# Stepping_Motor_DriverE.net
KiCad netlist of a schematic drawn in Altium Designer
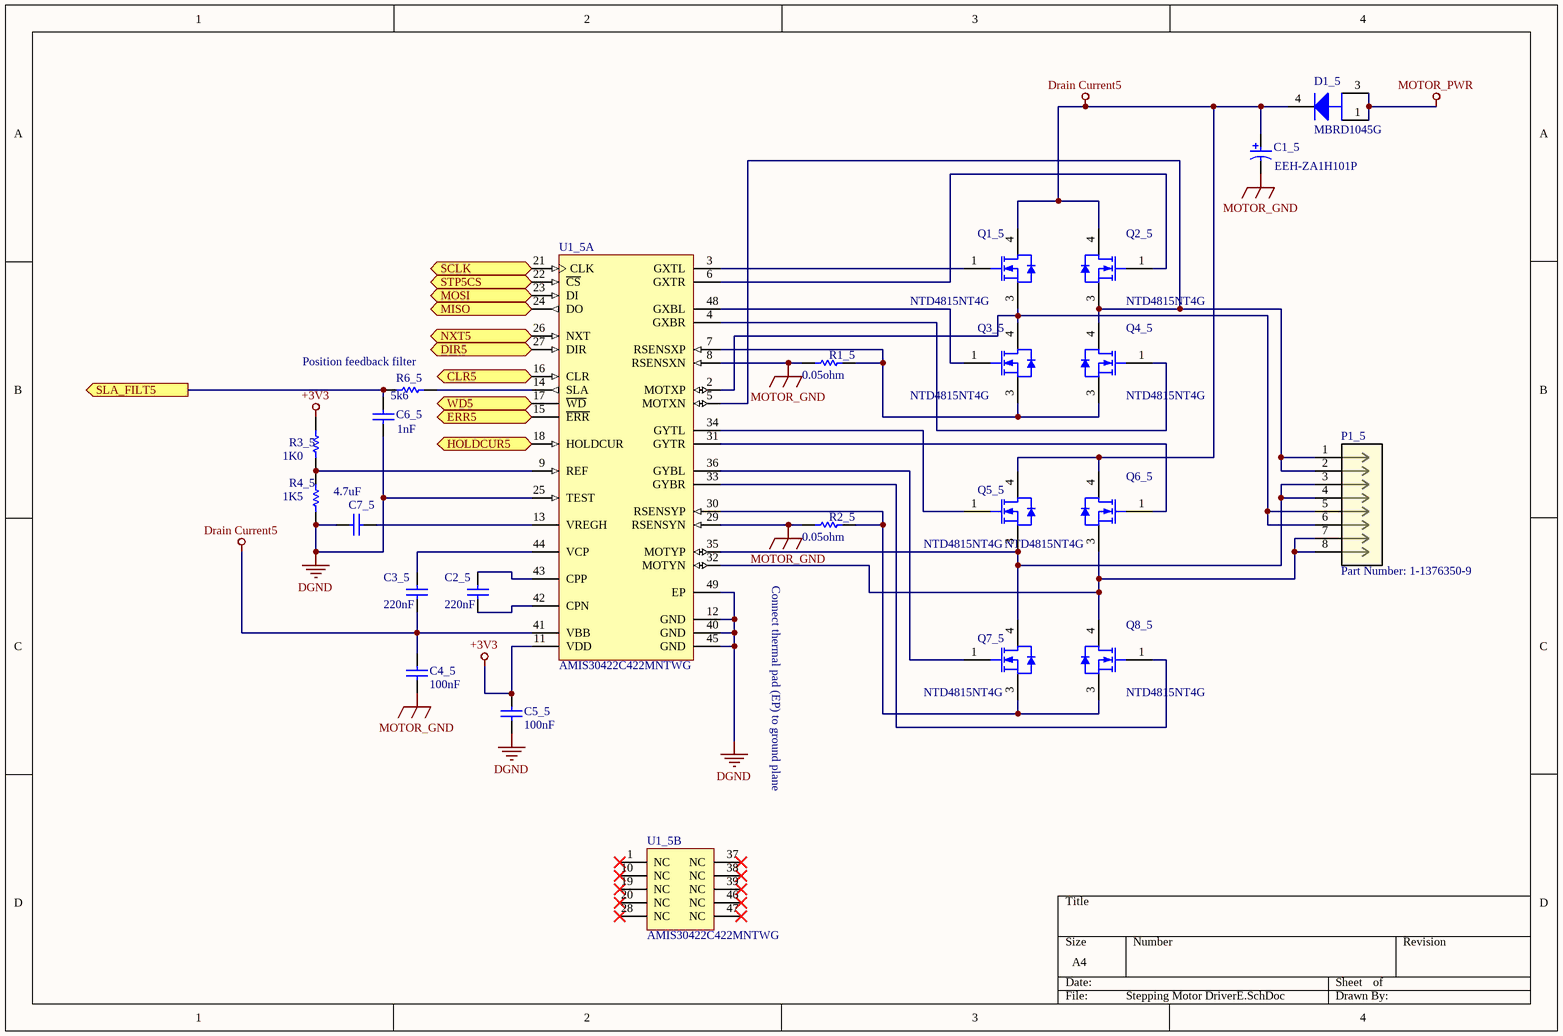
[diagram p0: Stepping Motor DriverE.SchDoc]

(export (version "E")
  (design (tool "Eeschema 10.0.6"))
  (components
    (comp (ref "C1_5")
      (value "EEH-ZA1H101P")
      (footprint "PNSC-ZA-G_L")
      (fields (field (name "TOLERANCE") "20%") (field (name "MANUFACTURER") "Panasonic"))
      (libsource (lib "Altium Content Vault") (part "CAP-P-2"))
    )
    (comp (ref "C2_5")
      (value "220nF")
      (footprint "CAPC0805(2012)75_L")
      (description "CAP 220nF 50V -20% to +80% 0805 (2012 Metric) Thickness 0.75mm SMD")
      (fields (field (name "TOLERANCE") "-20% to +80%") (field (name "Comment") "CAP 220nF 50V 0805(2012)"))
      (libsource (lib "Altium Content Vault") (part "CMP-1036-04556-1"))
    )
    (comp (ref "C3_5")
      (value "220nF")
      (footprint "CAPC0805(2012)75_L")
      (description "CAP 220nF 50V -20% to +80% 0805 (2012 Metric) Thickness 0.75mm SMD")
      (fields (field (name "TOLERANCE") "-20% to +80%") (field (name "Comment") "CAP 220nF 50V 0805(2012)"))
      (libsource (lib "Altium Content Vault") (part "CMP-1036-04556-1"))
    )
    (comp (ref "C4_5")
      (value "100nF")
      (footprint "CAPC1812(4532)110_N")
      (description "CAP 100nF 50V ±20% 1812 (4532 Metric) Thickness 1.1mm SMD")
      (fields (field (name "TOLERANCE") "Â±20%") (field (name "Comment") "CAP 100nF 50V 1812(4532)"))
      (libsource (lib "Altium Content Vault") (part "CMP-1040-01292-1"))
    )
    (comp (ref "C5_5")
      (value "100nF")
      (footprint "CAPC1812(4532)110_N")
      (description "CAP 100nF 50V ±20% 1812 (4532 Metric) Thickness 1.1mm SMD")
      (fields (field (name "TOLERANCE") "Â±20%") (field (name "Comment") "CAP 100nF 50V 1812(4532)"))
      (libsource (lib "Altium Content Vault") (part "CMP-1040-01292-1"))
    )
    (comp (ref "C6_5")
      (value "1nF")
      (footprint "CAPC1206(3216)170_N")
      (description "CAP 1nF 50V ±2% 1206 (3216 Metric) Thickness 1.7mm SMD")
      (fields (field (name "TOLERANCE") "Â±2%") (field (name "Comment") "CAP 1nF 50V 1206(3216)"))
      (libsource (lib "Altium Content Vault") (part "CMP-1037-02447-1"))
    )
    (comp (ref "C7_5")
      (value "4.7uF")
      (footprint "CAPC2220(5750)230_L")
      (description "CAP 4.7uF 50V ±10% 2220 (5750 Metric) Thickness 2.2mm SMD")
      (fields (field (name "TOLERANCE") "Â±10%") (field (name "Comment") "CAP 4.7uF 50V 2220(5750)"))
      (libsource (lib "Altium Content Vault") (part "CMP-1042-00755-1"))
    )
    (comp (ref "D1_5")
      (value "MBRD1045G")
      (footprint "ONSC-DPAK-3-369C-01_V")
      (description "SWITCHMODE(TM) Schottky Power Rectifier, 3-Pin DPAK, Pb-Free, Tube")
      (fields (field (name "MANUFACTURER") "On Semiconductor"))
      (libsource (lib "Altium Content Vault") (part "ONSC-D-A1A3K4-3_A"))
    )
    (comp (ref "P1_5")
      (value "Part Number: 1-1376350-9")
      (footprint "conn8_1-1376350-")
      (description "025 8POS CAP ASSY H TIN")
      (fields
        (field (name "MANUFACTURER_PART_NUMBER") "1-1376350-9")
        (field (name "COPYRIGHT") "Copyright (C) 2018 Accelerated Designs. All rights reserved")
      )
      (libsource (lib "2020-04-08_04-40-03") (part "1-1376350-9"))
    )
    (comp (ref "Q1_5")
      (value "NTD4815NT4G")
      (footprint "ONSC-DPAK-3-369AA-01_V")
      (description "Power MOSFET, 30 V, 35 A, Single N-Channel, 3-Pin DPAK, Pb-Free, Tape and Reel")
      (fields (field (name "MANUFACTURER") "On Semiconductor"))
      (libsource (lib "Altium Content Vault") (part "ONSC-NMOS-G1S3D4-3_B"))
    )
    (comp (ref "Q2_5")
      (value "NTD4815NT4G")
      (footprint "ONSC-DPAK-3-369AA-01_V")
      (description "Power MOSFET, 30 V, 35 A, Single N-Channel, 3-Pin DPAK, Pb-Free, Tape and Reel")
      (fields (field (name "MANUFACTURER") "On Semiconductor"))
      (libsource (lib "Altium Content Vault") (part "CMP-1058-00298-1"))
    )
    (comp (ref "Q3_5")
      (value "NTD4815NT4G")
      (footprint "ONSC-DPAK-3-369AA-01_V")
      (description "Power MOSFET, 30 V, 35 A, Single N-Channel, 3-Pin DPAK, Pb-Free, Tape and Reel")
      (fields (field (name "MANUFACTURER") "On Semiconductor"))
      (libsource (lib "Altium Content Vault") (part "ONSC-NMOS-G1S3D4-3_B"))
    )
    (comp (ref "Q4_5")
      (value "NTD4815NT4G")
      (footprint "ONSC-DPAK-3-369AA-01_V")
      (description "Power MOSFET, 30 V, 35 A, Single N-Channel, 3-Pin DPAK, Pb-Free, Tape and Reel")
      (fields (field (name "MANUFACTURER") "On Semiconductor"))
      (libsource (lib "Altium Content Vault") (part "CMP-1058-00298-1"))
    )
    (comp (ref "Q5_5")
      (value "NTD4815NT4G")
      (footprint "ONSC-DPAK-3-369AA-01_V")
      (description "Power MOSFET, 30 V, 35 A, Single N-Channel, 3-Pin DPAK, Pb-Free, Tape and Reel")
      (fields (field (name "MANUFACTURER") "On Semiconductor"))
      (libsource (lib "Altium Content Vault") (part "ONSC-NMOS-G1S3D4-3_B"))
    )
    (comp (ref "Q6_5")
      (value "NTD4815NT4G")
      (footprint "ONSC-DPAK-3-369AA-01_V")
      (description "Power MOSFET, 30 V, 35 A, Single N-Channel, 3-Pin DPAK, Pb-Free, Tape and Reel")
      (fields (field (name "MANUFACTURER") "On Semiconductor"))
      (libsource (lib "Altium Content Vault") (part "CMP-1058-00298-1"))
    )
    (comp (ref "Q7_5")
      (value "NTD4815NT4G")
      (footprint "ONSC-DPAK-3-369AA-01_V")
      (description "Power MOSFET, 30 V, 35 A, Single N-Channel, 3-Pin DPAK, Pb-Free, Tape and Reel")
      (fields (field (name "MANUFACTURER") "On Semiconductor"))
      (libsource (lib "Altium Content Vault") (part "ONSC-NMOS-G1S3D4-3_B"))
    )
    (comp (ref "Q8_5")
      (value "NTD4815NT4G")
      (footprint "ONSC-DPAK-3-369AA-01_V")
      (description "Power MOSFET, 30 V, 35 A, Single N-Channel, 3-Pin DPAK, Pb-Free, Tape and Reel")
      (fields (field (name "MANUFACTURER") "On Semiconductor"))
      (libsource (lib "Altium Content Vault") (part "CMP-1058-00298-1"))
    )
    (comp (ref "R1_5")
      (value "WSL2512R0500FEA")
      (footprint "RESC6432X89X76LL25T25")
      (description "Chip Resistor, 50 mOhm, +/- 1%, 1 W, -65 to 170 degC, 2512 (6432 Metric), RoHS, Tape and Reel")
      (fields (field (name "MANUFACTURER") "Vishay") (field (name "RESISTANCE") "0.05ohm"))
      (libsource (lib "Altium Content Vault") (part "CMP-2000-07420-1"))
    )
    (comp (ref "R2_5")
      (value "WSL2512R0500FEA")
      (footprint "RESC6432X89X76LL25T25")
      (description "Chip Resistor, 50 mOhm, +/- 1%, 1 W, -65 to 170 degC, 2512 (6432 Metric), RoHS, Tape and Reel")
      (fields (field (name "MANUFACTURER") "Vishay") (field (name "RESISTANCE") "0.05ohm"))
      (libsource (lib "Altium Content Vault") (part "CMP-2000-07420-1"))
    )
    (comp (ref "R3_5")
      (value "1K0")
      (footprint "RESC0805(2012)_M")
      (description "1K 0.125W 1% 0805 (2012 Metric)  SMD")
      (fields (field (name "TOLERANCE") "1 %") (field (name "POWER") "0.125 W"))
      (libsource (lib "Altium Content Vault") (part "CMP-1013-00510-1"))
    )
    (comp (ref "R4_5")
      (value "1K5")
      (footprint "RESC0805(2012)_M")
      (description "1K5 0.125W 1% 0805 (2012 Metric)  SMD")
      (fields (field (name "POWER") "0.125 W") (field (name "TOLERANCE") "1 %"))
      (libsource (lib "Altium Content Vault") (part "CMP-1013-00528-1"))
    )
    (comp (ref "R6_5")
      (value "5k6")
      (footprint "RESC0805(2012)_L")
      (description "5K6 0.125W 1% 0805 (2012 Metric)  SMD")
      (fields (field (name "POWER") "0.125 W") (field (name "TOLERANCE") "1 %"))
      (libsource (lib "Altium Content Vault") (part "CMP-1013-00595-1"))
    )
    (comp (ref "U1_5")
      (value "AMIS30422C422MNTWG")
      (footprint "ONSC-QFN-48-485AJ-01_V")
      (fields (field (name "MANUFACTURER") "ON Semiconductor"))
      (libsource (lib "Altium Content Vault") (part "ONSC-AMIS-30422-QFN-48"))
    )
  )
  (nets
    (net (code "1") (name "+3V3") (class "Default")
      (node (ref "C5_5") (pin "2") (pinfunction "2_2") (pintype "passive"))
      (node (ref "R3_5") (pin "2") (pinfunction "2_2") (pintype "passive"))
      (node (ref "U1_5") (pin "11") (pinfunction "VDD_11") (pintype "power_in"))
    )
    (net (code "2") (name "/CLR5") (class "Default")
      (node (ref "U1_5") (pin "16") (pinfunction "CLR_16") (pintype "input"))
    )
    (net (code "3") (name "/DIR5") (class "Default")
      (node (ref "U1_5") (pin "27") (pinfunction "DIR_27") (pintype "input"))
    )
    (net (code "4") (name "/ERR5") (class "Default")
      (node (ref "U1_5") (pin "15") (pinfunction "~{ERR}_15") (pintype "tri_state"))
    )
    (net (code "5") (name "/HOLDCUR5") (class "Default")
      (node (ref "U1_5") (pin "18") (pinfunction "HOLDCUR_18") (pintype "input"))
    )
    (net (code "6") (name "/MISO") (class "Default")
      (node (ref "U1_5") (pin "24") (pinfunction "DO_24") (pintype "output"))
    )
    (net (code "7") (name "/MOSI") (class "Default")
      (node (ref "U1_5") (pin "23") (pinfunction "DI_23") (pintype "input"))
    )
    (net (code "8") (name "/NXT5") (class "Default")
      (node (ref "U1_5") (pin "26") (pinfunction "NXT_26") (pintype "input"))
    )
    (net (code "9") (name "/SCLK") (class "Default")
      (node (ref "U1_5") (pin "21") (pinfunction "CLK_21") (pintype "input"))
    )
    (net (code "10") (name "/SLA_FILT5") (class "Default")
      (node (ref "C6_5") (pin "2") (pinfunction "2_2") (pintype "passive"))
      (node (ref "R6_5") (pin "1") (pinfunction "1_1") (pintype "passive"))
    )
    (net (code "11") (name "/STP5CS") (class "Default")
      (node (ref "U1_5") (pin "22") (pinfunction "~{CS}_22") (pintype "input"))
    )
    (net (code "12") (name "/WD5") (class "Default")
      (node (ref "U1_5") (pin "17") (pinfunction "~{WD}_17") (pintype "tri_state"))
    )
    (net (code "13") (name "DGND") (class "Default")
      (node (ref "C5_5") (pin "1") (pinfunction "1_1") (pintype "passive"))
      (node (ref "C6_5") (pin "1") (pinfunction "1_1") (pintype "passive"))
      (node (ref "C7_5") (pin "1") (pinfunction "1_1") (pintype "passive"))
      (node (ref "R4_5") (pin "1") (pinfunction "1_1") (pintype "passive"))
      (node (ref "U1_5") (pin "12") (pinfunction "GND_12") (pintype "power_in"))
      (node (ref "U1_5") (pin "25") (pinfunction "TEST_25") (pintype "input"))
      (node (ref "U1_5") (pin "40") (pinfunction "GND_40") (pintype "power_in"))
      (node (ref "U1_5") (pin "45") (pinfunction "GND_45") (pintype "power_in"))
      (node (ref "U1_5") (pin "49") (pinfunction "EP_49") (pintype "passive"))
    )
    (net (code "14") (name "Drain Current5") (class "Default")
      (node (ref "C1_5") (pin "1") (pinfunction "1_1") (pintype "passive"))
      (node (ref "C3_5") (pin "1") (pinfunction "1_1") (pintype "passive"))
      (node (ref "C4_5") (pin "2") (pinfunction "2_2") (pintype "passive"))
      (node (ref "D1_5") (pin "4") (pinfunction "K_4") (pintype "passive"))
      (node (ref "Q1_5") (pin "4") (pinfunction "D_4") (pintype "passive"))
      (node (ref "Q2_5") (pin "4") (pinfunction "D_4") (pintype "passive"))
      (node (ref "Q5_5") (pin "4") (pinfunction "D_4") (pintype "passive"))
      (node (ref "Q6_5") (pin "4") (pinfunction "D_4") (pintype "passive"))
      (node (ref "U1_5") (pin "41") (pinfunction "VBB_41") (pintype "power_in"))
    )
    (net (code "15") (name "MOTOR_GND") (class "Default")
      (node (ref "C1_5") (pin "2") (pinfunction "2_2") (pintype "passive"))
      (node (ref "C4_5") (pin "1") (pinfunction "1_1") (pintype "passive"))
      (node (ref "R1_5") (pin "1") (pinfunction "1_1") (pintype "passive"))
      (node (ref "R2_5") (pin "1") (pinfunction "1_1") (pintype "passive"))
      (node (ref "U1_5") (pin "29") (pinfunction "RSENSYN_29") (pintype "input"))
      (node (ref "U1_5") (pin "8") (pinfunction "RSENSXN_8") (pintype "input"))
    )
    (net (code "16") (name "MOTOR_PWR") (class "Default")
      (node (ref "D1_5") (pin "1") (pinfunction "A_1") (pintype "passive"))
      (node (ref "D1_5") (pin "3") (pinfunction "A_3") (pintype "passive"))
    )
    (net (code "17") (name "Net-(Q1_5-G)") (class "Default")
      (node (ref "Q1_5") (pin "1") (pinfunction "G_1") (pintype "passive"))
      (node (ref "U1_5") (pin "3") (pinfunction "GXTL_3") (pintype "tri_state"))
    )
    (net (code "18") (name "Net-(Q1_5-S)") (class "Default")
      (node (ref "P1_5") (pin "5") (pinfunction "5_5") (pintype "passive"))
      (node (ref "P1_5") (pin "6") (pinfunction "6_6") (pintype "passive"))
      (node (ref "Q1_5") (pin "3") (pinfunction "S_3") (pintype "passive"))
      (node (ref "Q3_5") (pin "4") (pinfunction "D_4") (pintype "passive"))
      (node (ref "U1_5") (pin "2") (pinfunction "MOTXP_2") (pintype "bidirectional"))
    )
    (net (code "19") (name "Net-(Q2_5-G)") (class "Default")
      (node (ref "Q2_5") (pin "1") (pinfunction "G_1") (pintype "passive"))
      (node (ref "U1_5") (pin "6") (pinfunction "GXTR_6") (pintype "tri_state"))
    )
    (net (code "20") (name "Net-(Q2_5-S)") (class "Default")
      (node (ref "P1_5") (pin "1") (pinfunction "1_1") (pintype "passive"))
      (node (ref "P1_5") (pin "2") (pinfunction "2_2") (pintype "passive"))
      (node (ref "Q2_5") (pin "3") (pinfunction "S_3") (pintype "passive"))
      (node (ref "Q4_5") (pin "4") (pinfunction "D_4") (pintype "passive"))
      (node (ref "U1_5") (pin "5") (pinfunction "MOTXN_5") (pintype "bidirectional"))
    )
    (net (code "21") (name "Net-(Q3_5-G)") (class "Default")
      (node (ref "Q3_5") (pin "1") (pinfunction "G_1") (pintype "passive"))
      (node (ref "U1_5") (pin "48") (pinfunction "GXBL_48") (pintype "tri_state"))
    )
    (net (code "22") (name "Net-(Q3_5-S)") (class "Default")
      (node (ref "Q3_5") (pin "3") (pinfunction "S_3") (pintype "passive"))
      (node (ref "Q4_5") (pin "3") (pinfunction "S_3") (pintype "passive"))
      (node (ref "R1_5") (pin "2") (pinfunction "2_2") (pintype "passive"))
      (node (ref "U1_5") (pin "7") (pinfunction "RSENSXP_7") (pintype "input"))
    )
    (net (code "23") (name "Net-(Q4_5-G)") (class "Default")
      (node (ref "Q4_5") (pin "1") (pinfunction "G_1") (pintype "passive"))
      (node (ref "U1_5") (pin "4") (pinfunction "GXBR_4") (pintype "tri_state"))
    )
    (net (code "24") (name "Net-(Q5_5-G)") (class "Default")
      (node (ref "Q5_5") (pin "1") (pinfunction "G_1") (pintype "passive"))
      (node (ref "U1_5") (pin "34") (pinfunction "GYTL_34") (pintype "tri_state"))
    )
    (net (code "25") (name "Net-(Q5_5-S)") (class "Default")
      (node (ref "P1_5") (pin "3") (pinfunction "3_3") (pintype "passive"))
      (node (ref "P1_5") (pin "4") (pinfunction "4_4") (pintype "passive"))
      (node (ref "Q5_5") (pin "3") (pinfunction "S_3") (pintype "passive"))
      (node (ref "Q7_5") (pin "4") (pinfunction "D_4") (pintype "passive"))
      (node (ref "U1_5") (pin "35") (pinfunction "MOTYP_35") (pintype "bidirectional"))
    )
    (net (code "26") (name "Net-(Q6_5-G)") (class "Default")
      (node (ref "Q6_5") (pin "1") (pinfunction "G_1") (pintype "passive"))
      (node (ref "U1_5") (pin "31") (pinfunction "GYTR_31") (pintype "tri_state"))
    )
    (net (code "27") (name "Net-(Q6_5-S)") (class "Default")
      (node (ref "P1_5") (pin "7") (pinfunction "7_7") (pintype "passive"))
      (node (ref "P1_5") (pin "8") (pinfunction "8_8") (pintype "passive"))
      (node (ref "Q6_5") (pin "3") (pinfunction "S_3") (pintype "passive"))
      (node (ref "Q8_5") (pin "4") (pinfunction "D_4") (pintype "passive"))
      (node (ref "U1_5") (pin "32") (pinfunction "MOTYN_32") (pintype "bidirectional"))
    )
    (net (code "28") (name "Net-(Q7_5-G)") (class "Default")
      (node (ref "Q7_5") (pin "1") (pinfunction "G_1") (pintype "passive"))
      (node (ref "U1_5") (pin "36") (pinfunction "GYBL_36") (pintype "tri_state"))
    )
    (net (code "29") (name "Net-(Q7_5-S)") (class "Default")
      (node (ref "Q7_5") (pin "3") (pinfunction "S_3") (pintype "passive"))
      (node (ref "Q8_5") (pin "3") (pinfunction "S_3") (pintype "passive"))
      (node (ref "R2_5") (pin "2") (pinfunction "2_2") (pintype "passive"))
      (node (ref "U1_5") (pin "30") (pinfunction "RSENSYP_30") (pintype "input"))
    )
    (net (code "30") (name "Net-(Q8_5-G)") (class "Default")
      (node (ref "Q8_5") (pin "1") (pinfunction "G_1") (pintype "passive"))
      (node (ref "U1_5") (pin "33") (pinfunction "GYBR_33") (pintype "tri_state"))
    )
    (net (code "31") (name "Net-(U1_5A-CPN)") (class "Default")
      (node (ref "C2_5") (pin "1") (pinfunction "1_1") (pintype "passive"))
      (node (ref "U1_5") (pin "42") (pinfunction "CPN_42") (pintype "passive"))
    )
    (net (code "32") (name "Net-(U1_5A-CPP)") (class "Default")
      (node (ref "C2_5") (pin "2") (pinfunction "2_2") (pintype "passive"))
      (node (ref "U1_5") (pin "43") (pinfunction "CPP_43") (pintype "passive"))
    )
    (net (code "33") (name "Net-(U1_5A-REF)") (class "Default")
      (node (ref "R3_5") (pin "1") (pinfunction "1_1") (pintype "passive"))
      (node (ref "R4_5") (pin "2") (pinfunction "2_2") (pintype "passive"))
      (node (ref "U1_5") (pin "9") (pinfunction "REF_9") (pintype "input"))
    )
    (net (code "34") (name "Net-(U1_5A-SLA)") (class "Default")
      (node (ref "R6_5") (pin "2") (pinfunction "2_2") (pintype "passive"))
      (node (ref "U1_5") (pin "14") (pinfunction "SLA_14") (pintype "output"))
    )
    (net (code "35") (name "Net-(U1_5A-VCP)") (class "Default")
      (node (ref "C3_5") (pin "2") (pinfunction "2_2") (pintype "passive"))
      (node (ref "U1_5") (pin "44") (pinfunction "VCP_44") (pintype "passive"))
    )
    (net (code "36") (name "Net-(U1_5A-VREGH)") (class "Default")
      (node (ref "C7_5") (pin "2") (pinfunction "2_2") (pintype "passive"))
      (node (ref "U1_5") (pin "13") (pinfunction "VREGH_13") (pintype "power_in"))
    )
    (net (code "37") (name "unconnected-(U1_5B-NC-Pad1)") (class "Default")
      (node (ref "U1_5") (pin "1") (pinfunction "NC_1") (pintype "passive+no_connect"))
    )
    (net (code "38") (name "unconnected-(U1_5B-NC-Pad10)") (class "Default")
      (node (ref "U1_5") (pin "10") (pinfunction "NC_10") (pintype "passive+no_connect"))
    )
    (net (code "39") (name "unconnected-(U1_5B-NC-Pad19)") (class "Default")
      (node (ref "U1_5") (pin "19") (pinfunction "NC_19") (pintype "passive+no_connect"))
    )
    (net (code "40") (name "unconnected-(U1_5B-NC-Pad20)") (class "Default")
      (node (ref "U1_5") (pin "20") (pinfunction "NC_20") (pintype "passive+no_connect"))
    )
    (net (code "41") (name "unconnected-(U1_5B-NC-Pad28)") (class "Default")
      (node (ref "U1_5") (pin "28") (pinfunction "NC_28") (pintype "passive+no_connect"))
    )
    (net (code "42") (name "unconnected-(U1_5B-NC-Pad37)") (class "Default")
      (node (ref "U1_5") (pin "37") (pinfunction "NC_37") (pintype "passive+no_connect"))
    )
    (net (code "43") (name "unconnected-(U1_5B-NC-Pad38)") (class "Default")
      (node (ref "U1_5") (pin "38") (pinfunction "NC_38") (pintype "passive+no_connect"))
    )
    (net (code "44") (name "unconnected-(U1_5B-NC-Pad39)") (class "Default")
      (node (ref "U1_5") (pin "39") (pinfunction "NC_39") (pintype "passive+no_connect"))
    )
    (net (code "45") (name "unconnected-(U1_5B-NC-Pad46)") (class "Default")
      (node (ref "U1_5") (pin "46") (pinfunction "NC_46") (pintype "passive+no_connect"))
    )
    (net (code "46") (name "unconnected-(U1_5B-NC-Pad47)") (class "Default")
      (node (ref "U1_5") (pin "47") (pinfunction "NC_47") (pintype "passive+no_connect"))
    )
  )
)
